# Sheet1.net
KiCad netlist of a schematic drawn in Altium Designer
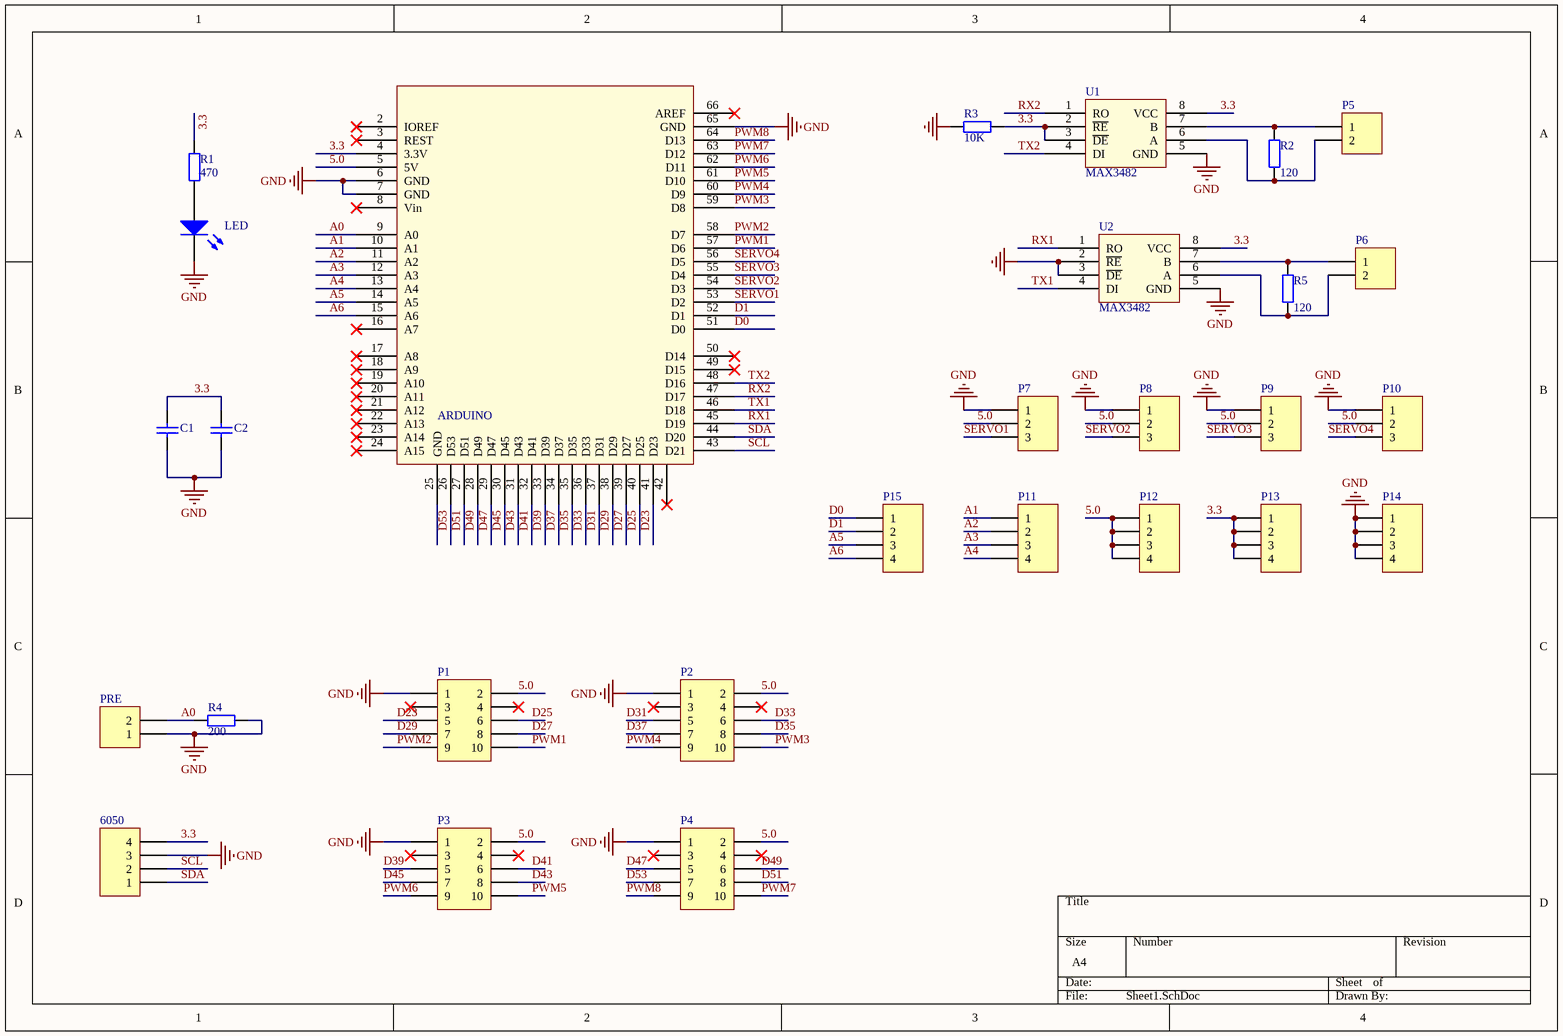
[diagram p0: Sheet1.SchDoc]

(export (version "E")
  (design (tool "Eeschema 10.0.6"))
  (components
    (comp (ref "6050")
      (value "Header 4")
      (footprint "HDR1X4")
      (description "Header, 4-Pin")
      (fields (field (name "PUBLISHER") "Altium Limited"))
      (libsource (lib "") (part "Header 4_1"))
    )
    (comp (ref "ARDUINO")
      (value "2560")
      (footprint "ARDUINO")
      (libsource (lib "Schlib1") (part "Component_1"))
    )
    (comp (ref "C1")
      (value "Cap")
      (footprint "0805")
      (description "Capacitor")
      (fields (field (name "PUBLISHER") "Altium Limited"))
      (libsource (lib "Miscellaneous Devices") (part "Cap"))
    )
    (comp (ref "C2")
      (value "Cap")
      (footprint "0805")
      (description "Capacitor")
      (fields (field (name "PUBLISHER") "Altium Limited"))
      (libsource (lib "Miscellaneous Devices") (part "Cap"))
    )
    (comp (ref "LED")
      (value "LED0")
      (footprint "0805")
      (description "Typical INFRARED GaAs LED")
      (fields (field (name "PUBLISHER") "Altium Limited"))
      (libsource (lib "Miscellaneous Devices") (part "LED0"))
    )
    (comp (ref "P1")
      (value "Header 5X2")
      (footprint "HDR2X5")
      (description "Header, 5-Pin, Dual row")
      (fields (field (name "PUBLISHER") "Altium Limited"))
      (libsource (lib "Miscellaneous Connectors") (part "Header 5X2"))
    )
    (comp (ref "P2")
      (value "Header 5X2")
      (footprint "HDR2X5")
      (description "Header, 5-Pin, Dual row")
      (fields (field (name "PUBLISHER") "Altium Limited"))
      (libsource (lib "Miscellaneous Connectors") (part "Header 5X2"))
    )
    (comp (ref "P3")
      (value "Header 5X2")
      (footprint "HDR2X5")
      (description "Header, 5-Pin, Dual row")
      (fields (field (name "PUBLISHER") "Altium Limited"))
      (libsource (lib "Miscellaneous Connectors") (part "Header 5X2"))
    )
    (comp (ref "P4")
      (value "Header 5X2")
      (footprint "HDR2X5")
      (description "Header, 5-Pin, Dual row")
      (fields (field (name "PUBLISHER") "Altium Limited"))
      (libsource (lib "Miscellaneous Connectors") (part "Header 5X2"))
    )
    (comp (ref "P5")
      (value "Header 2")
      (footprint "蓝色电源插座")
      (description "Header, 2-Pin")
      (fields (field (name "PUBLISHER") "Altium Limited"))
      (libsource (lib "Miscellaneous Connectors") (part "Header 2"))
    )
    (comp (ref "P6")
      (value "Header 2")
      (footprint "蓝色电源插座")
      (description "Header, 2-Pin")
      (fields (field (name "PUBLISHER") "Altium Limited"))
      (libsource (lib "Miscellaneous Connectors") (part "Header 2"))
    )
    (comp (ref "P7")
      (value "Header 3")
      (footprint "HDR1X3")
      (description "Header, 3-Pin")
      (fields (field (name "PUBLISHER") "Altium Limited"))
      (libsource (lib "Miscellaneous Connectors") (part "Header 3"))
    )
    (comp (ref "P8")
      (value "Header 3")
      (footprint "HDR1X3")
      (description "Header, 3-Pin")
      (fields (field (name "PUBLISHER") "Altium Limited"))
      (libsource (lib "Miscellaneous Connectors") (part "Header 3"))
    )
    (comp (ref "P9")
      (value "Header 3")
      (footprint "HDR1X3")
      (description "Header, 3-Pin")
      (fields (field (name "PUBLISHER") "Altium Limited"))
      (libsource (lib "Miscellaneous Connectors") (part "Header 3"))
    )
    (comp (ref "P10")
      (value "Header 3")
      (footprint "HDR1X3")
      (description "Header, 3-Pin")
      (fields (field (name "PUBLISHER") "Altium Limited"))
      (libsource (lib "Miscellaneous Connectors") (part "Header 3"))
    )
    (comp (ref "P11")
      (value "Header 4")
      (footprint "HDR1X4")
      (description "Header, 4-Pin")
      (fields (field (name "PUBLISHER") "Altium Limited"))
      (libsource (lib "Miscellaneous Connectors") (part "Header 4"))
    )
    (comp (ref "P12")
      (value "Header 4")
      (footprint "HDR1X4")
      (description "Header, 4-Pin")
      (fields (field (name "PUBLISHER") "Altium Limited"))
      (libsource (lib "Miscellaneous Connectors") (part "Header 4"))
    )
    (comp (ref "P13")
      (value "Header 4")
      (footprint "HDR1X4")
      (description "Header, 4-Pin")
      (fields (field (name "PUBLISHER") "Altium Limited"))
      (libsource (lib "Miscellaneous Connectors") (part "Header 4"))
    )
    (comp (ref "P14")
      (value "Header 4")
      (footprint "HDR1X4")
      (description "Header, 4-Pin")
      (fields (field (name "PUBLISHER") "Altium Limited"))
      (libsource (lib "Miscellaneous Connectors") (part "Header 4"))
    )
    (comp (ref "P15")
      (value "Header 4")
      (footprint "HDR1X4")
      (description "Header, 4-Pin")
      (fields (field (name "PUBLISHER") "Altium Limited"))
      (libsource (lib "Miscellaneous Connectors") (part "Header 4"))
    )
    (comp (ref "PRE")
      (value "Header 2")
      (footprint "HDR1X2")
      (description "Header, 2-Pin")
      (fields (field (name "PUBLISHER") "Altium Limited"))
      (libsource (lib "") (part "Header 2_1"))
    )
    (comp (ref "R1")
      (value "470")
      (footprint "0805")
      (description "Resistor")
      (fields (field (name "Comment") "Res2") (field (name "PUBLISHER") "Altium Limited"))
      (libsource (lib "") (part "Res2_3"))
    )
    (comp (ref "R2")
      (value "120")
      (footprint "0805")
      (description "Resistor")
      (fields (field (name "Comment") "Res2") (field (name "PUBLISHER") "Altium Limited"))
      (libsource (lib "") (part "Res2_1"))
    )
    (comp (ref "R3")
      (value "10K")
      (footprint "0805")
      (description "Resistor")
      (fields (field (name "Comment") "Res2") (field (name "PUBLISHER") "Altium Limited"))
      (libsource (lib "") (part "Res2_2"))
    )
    (comp (ref "R4")
      (value "200")
      (footprint "0805")
      (description "Resistor")
      (fields (field (name "Comment") "Res2") (field (name "PUBLISHER") "Altium Limited"))
      (libsource (lib "Miscellaneous Devices") (part "Res2"))
    )
    (comp (ref "R5")
      (value "120")
      (footprint "0805")
      (description "Resistor")
      (fields (field (name "Comment") "Res2") (field (name "PUBLISHER") "Altium Limited"))
      (libsource (lib "") (part "Res2_1"))
    )
    (comp (ref "U1") (value "MAX3482") (footprint "3485") (libsource (lib "Schlib1") (part "MAX3482")))
    (comp (ref "U2") (value "MAX3482") (footprint "3485") (libsource (lib "Schlib1") (part "MAX3482")))
  )
  (nets
    (net (code "1") (name "/3.3") (class "Default")
      (node (ref "6050") (pin "4") (pinfunction "4_4") (pintype "passive"))
      (node (ref "ARDUINO") (pin "4") (pinfunction "3.3V_4") (pintype "passive"))
      (node (ref "C1") (pin "2") (pinfunction "2_2") (pintype "passive"))
      (node (ref "C2") (pin "2") (pinfunction "2_2") (pintype "passive"))
      (node (ref "P13") (pin "1") (pinfunction "1_1") (pintype "passive"))
      (node (ref "P13") (pin "2") (pinfunction "2_2") (pintype "passive"))
      (node (ref "P13") (pin "3") (pinfunction "3_3") (pintype "passive"))
      (node (ref "P13") (pin "4") (pinfunction "4_4") (pintype "passive"))
      (node (ref "R1") (pin "1") (pinfunction "1_1") (pintype "passive"))
      (node (ref "R3") (pin "1") (pinfunction "1_1") (pintype "passive"))
      (node (ref "U1") (pin "2") (pinfunction "~{RE}_2") (pintype "passive"))
      (node (ref "U1") (pin "3") (pinfunction "~{DE}_3") (pintype "passive"))
      (node (ref "U1") (pin "8") (pinfunction "VCC_8") (pintype "passive"))
      (node (ref "U2") (pin "8") (pinfunction "VCC_8") (pintype "passive"))
    )
    (net (code "2") (name "/5.0") (class "Default")
      (node (ref "ARDUINO") (pin "5") (pinfunction "5V_5") (pintype "passive"))
      (node (ref "P1") (pin "2") (pinfunction "2_2") (pintype "passive"))
      (node (ref "P10") (pin "2") (pinfunction "2_2") (pintype "passive"))
      (node (ref "P12") (pin "1") (pinfunction "1_1") (pintype "passive"))
      (node (ref "P12") (pin "2") (pinfunction "2_2") (pintype "passive"))
      (node (ref "P12") (pin "3") (pinfunction "3_3") (pintype "passive"))
      (node (ref "P12") (pin "4") (pinfunction "4_4") (pintype "passive"))
      (node (ref "P2") (pin "2") (pinfunction "2_2") (pintype "passive"))
      (node (ref "P3") (pin "2") (pinfunction "2_2") (pintype "passive"))
      (node (ref "P4") (pin "2") (pinfunction "2_2") (pintype "passive"))
      (node (ref "P7") (pin "2") (pinfunction "2_2") (pintype "passive"))
      (node (ref "P8") (pin "2") (pinfunction "2_2") (pintype "passive"))
      (node (ref "P9") (pin "2") (pinfunction "2_2") (pintype "passive"))
    )
    (net (code "3") (name "/A0") (class "Default")
      (node (ref "ARDUINO") (pin "9") (pinfunction "A0_9") (pintype "passive"))
      (node (ref "PRE") (pin "2") (pinfunction "2_2") (pintype "passive"))
      (node (ref "R4") (pin "1") (pinfunction "1_1") (pintype "passive"))
    )
    (net (code "4") (name "/A1") (class "Default")
      (node (ref "ARDUINO") (pin "10") (pinfunction "A1_10") (pintype "passive"))
      (node (ref "P11") (pin "1") (pinfunction "1_1") (pintype "passive"))
    )
    (net (code "5") (name "/A2") (class "Default")
      (node (ref "ARDUINO") (pin "11") (pinfunction "A2_11") (pintype "passive"))
      (node (ref "P11") (pin "2") (pinfunction "2_2") (pintype "passive"))
    )
    (net (code "6") (name "/A3") (class "Default")
      (node (ref "ARDUINO") (pin "12") (pinfunction "A3_12") (pintype "passive"))
      (node (ref "P11") (pin "3") (pinfunction "3_3") (pintype "passive"))
    )
    (net (code "7") (name "/A4") (class "Default")
      (node (ref "ARDUINO") (pin "13") (pinfunction "A4_13") (pintype "passive"))
      (node (ref "P11") (pin "4") (pinfunction "4_4") (pintype "passive"))
    )
    (net (code "8") (name "/A5") (class "Default")
      (node (ref "ARDUINO") (pin "14") (pinfunction "A5_14") (pintype "passive"))
      (node (ref "P15") (pin "3") (pinfunction "3_3") (pintype "passive"))
    )
    (net (code "9") (name "/A6") (class "Default")
      (node (ref "ARDUINO") (pin "15") (pinfunction "A6_15") (pintype "passive"))
      (node (ref "P15") (pin "4") (pinfunction "4_4") (pintype "passive"))
    )
    (net (code "10") (name "/D0") (class "Default")
      (node (ref "ARDUINO") (pin "51") (pinfunction "D0_51") (pintype "passive"))
      (node (ref "P15") (pin "1") (pinfunction "1_1") (pintype "passive"))
    )
    (net (code "11") (name "/D1") (class "Default")
      (node (ref "ARDUINO") (pin "52") (pinfunction "D1_52") (pintype "passive"))
      (node (ref "P15") (pin "2") (pinfunction "2_2") (pintype "passive"))
    )
    (net (code "12") (name "/D23") (class "Default")
      (node (ref "ARDUINO") (pin "41") (pinfunction "D23_41") (pintype "passive"))
      (node (ref "P1") (pin "5") (pinfunction "5_5") (pintype "passive"))
    )
    (net (code "13") (name "/D25") (class "Default")
      (node (ref "ARDUINO") (pin "40") (pinfunction "D25_40") (pintype "passive"))
      (node (ref "P1") (pin "6") (pinfunction "6_6") (pintype "passive"))
    )
    (net (code "14") (name "/D27") (class "Default")
      (node (ref "ARDUINO") (pin "39") (pinfunction "D27_39") (pintype "passive"))
      (node (ref "P1") (pin "8") (pinfunction "8_8") (pintype "passive"))
    )
    (net (code "15") (name "/D29") (class "Default")
      (node (ref "ARDUINO") (pin "38") (pinfunction "D29_38") (pintype "passive"))
      (node (ref "P1") (pin "7") (pinfunction "7_7") (pintype "passive"))
    )
    (net (code "16") (name "/D31") (class "Default")
      (node (ref "ARDUINO") (pin "37") (pinfunction "D31_37") (pintype "passive"))
      (node (ref "P2") (pin "5") (pinfunction "5_5") (pintype "passive"))
    )
    (net (code "17") (name "/D33") (class "Default")
      (node (ref "ARDUINO") (pin "36") (pinfunction "D33_36") (pintype "passive"))
      (node (ref "P2") (pin "6") (pinfunction "6_6") (pintype "passive"))
    )
    (net (code "18") (name "/D35") (class "Default")
      (node (ref "ARDUINO") (pin "35") (pinfunction "D35_35") (pintype "passive"))
      (node (ref "P2") (pin "8") (pinfunction "8_8") (pintype "passive"))
    )
    (net (code "19") (name "/D37") (class "Default")
      (node (ref "ARDUINO") (pin "34") (pinfunction "D37_34") (pintype "passive"))
      (node (ref "P2") (pin "7") (pinfunction "7_7") (pintype "passive"))
    )
    (net (code "20") (name "/D39") (class "Default")
      (node (ref "ARDUINO") (pin "33") (pinfunction "D39_33") (pintype "passive"))
      (node (ref "P3") (pin "5") (pinfunction "5_5") (pintype "passive"))
    )
    (net (code "21") (name "/D41") (class "Default")
      (node (ref "ARDUINO") (pin "32") (pinfunction "D41_32") (pintype "passive"))
      (node (ref "P3") (pin "6") (pinfunction "6_6") (pintype "passive"))
    )
    (net (code "22") (name "/D43") (class "Default")
      (node (ref "ARDUINO") (pin "31") (pinfunction "D43_31") (pintype "passive"))
      (node (ref "P3") (pin "8") (pinfunction "8_8") (pintype "passive"))
    )
    (net (code "23") (name "/D45") (class "Default")
      (node (ref "ARDUINO") (pin "30") (pinfunction "D45_30") (pintype "passive"))
      (node (ref "P3") (pin "7") (pinfunction "7_7") (pintype "passive"))
    )
    (net (code "24") (name "/D47") (class "Default")
      (node (ref "ARDUINO") (pin "29") (pinfunction "D47_29") (pintype "passive"))
      (node (ref "P4") (pin "5") (pinfunction "5_5") (pintype "passive"))
    )
    (net (code "25") (name "/D49") (class "Default")
      (node (ref "ARDUINO") (pin "28") (pinfunction "D49_28") (pintype "passive"))
      (node (ref "P4") (pin "6") (pinfunction "6_6") (pintype "passive"))
    )
    (net (code "26") (name "/D51") (class "Default")
      (node (ref "ARDUINO") (pin "27") (pinfunction "D51_27") (pintype "passive"))
      (node (ref "P4") (pin "8") (pinfunction "8_8") (pintype "passive"))
    )
    (net (code "27") (name "/D53") (class "Default")
      (node (ref "ARDUINO") (pin "26") (pinfunction "D53_26") (pintype "passive"))
      (node (ref "P4") (pin "7") (pinfunction "7_7") (pintype "passive"))
    )
    (net (code "28") (name "/PWM1") (class "Default")
      (node (ref "ARDUINO") (pin "57") (pinfunction "D6_57") (pintype "passive"))
      (node (ref "P1") (pin "10") (pinfunction "10_10") (pintype "passive"))
    )
    (net (code "29") (name "/PWM2") (class "Default")
      (node (ref "ARDUINO") (pin "58") (pinfunction "D7_58") (pintype "passive"))
      (node (ref "P1") (pin "9") (pinfunction "9_9") (pintype "passive"))
    )
    (net (code "30") (name "/PWM3") (class "Default")
      (node (ref "ARDUINO") (pin "59") (pinfunction "D8_59") (pintype "passive"))
      (node (ref "P2") (pin "10") (pinfunction "10_10") (pintype "passive"))
    )
    (net (code "31") (name "/PWM4") (class "Default")
      (node (ref "ARDUINO") (pin "60") (pinfunction "D9_60") (pintype "passive"))
      (node (ref "P2") (pin "9") (pinfunction "9_9") (pintype "passive"))
    )
    (net (code "32") (name "/PWM5") (class "Default")
      (node (ref "ARDUINO") (pin "61") (pinfunction "D10_61") (pintype "passive"))
      (node (ref "P3") (pin "10") (pinfunction "10_10") (pintype "passive"))
    )
    (net (code "33") (name "/PWM6") (class "Default")
      (node (ref "ARDUINO") (pin "62") (pinfunction "D11_62") (pintype "passive"))
      (node (ref "P3") (pin "9") (pinfunction "9_9") (pintype "passive"))
    )
    (net (code "34") (name "/PWM7") (class "Default")
      (node (ref "ARDUINO") (pin "63") (pinfunction "D12_63") (pintype "passive"))
      (node (ref "P4") (pin "10") (pinfunction "10_10") (pintype "passive"))
    )
    (net (code "35") (name "/PWM8") (class "Default")
      (node (ref "ARDUINO") (pin "64") (pinfunction "D13_64") (pintype "passive"))
      (node (ref "P4") (pin "9") (pinfunction "9_9") (pintype "passive"))
    )
    (net (code "36") (name "/RX1") (class "Default")
      (node (ref "ARDUINO") (pin "45") (pinfunction "D19_45") (pintype "passive"))
      (node (ref "U2") (pin "1") (pinfunction "RO_1") (pintype "passive"))
    )
    (net (code "37") (name "/RX2") (class "Default")
      (node (ref "ARDUINO") (pin "47") (pinfunction "D17_47") (pintype "passive"))
      (node (ref "U1") (pin "1") (pinfunction "RO_1") (pintype "passive"))
    )
    (net (code "38") (name "/SCL") (class "Default")
      (node (ref "6050") (pin "2") (pinfunction "2_2") (pintype "passive"))
      (node (ref "ARDUINO") (pin "43") (pinfunction "D21_43") (pintype "passive"))
    )
    (net (code "39") (name "/SDA") (class "Default")
      (node (ref "6050") (pin "1") (pinfunction "1_1") (pintype "passive"))
      (node (ref "ARDUINO") (pin "44") (pinfunction "D20_44") (pintype "passive"))
    )
    (net (code "40") (name "/SERVO1") (class "Default")
      (node (ref "ARDUINO") (pin "53") (pinfunction "D2_53") (pintype "passive"))
      (node (ref "P7") (pin "3") (pinfunction "3_3") (pintype "passive"))
    )
    (net (code "41") (name "/SERVO2") (class "Default")
      (node (ref "ARDUINO") (pin "54") (pinfunction "D3_54") (pintype "passive"))
      (node (ref "P8") (pin "3") (pinfunction "3_3") (pintype "passive"))
    )
    (net (code "42") (name "/SERVO3") (class "Default")
      (node (ref "ARDUINO") (pin "55") (pinfunction "D4_55") (pintype "passive"))
      (node (ref "P9") (pin "3") (pinfunction "3_3") (pintype "passive"))
    )
    (net (code "43") (name "/SERVO4") (class "Default")
      (node (ref "ARDUINO") (pin "56") (pinfunction "D5_56") (pintype "passive"))
      (node (ref "P10") (pin "3") (pinfunction "3_3") (pintype "passive"))
    )
    (net (code "44") (name "/TX1") (class "Default")
      (node (ref "ARDUINO") (pin "46") (pinfunction "D18_46") (pintype "passive"))
      (node (ref "U2") (pin "4") (pinfunction "DI_4") (pintype "passive"))
    )
    (net (code "45") (name "/TX2") (class "Default")
      (node (ref "ARDUINO") (pin "48") (pinfunction "D16_48") (pintype "passive"))
      (node (ref "U1") (pin "4") (pinfunction "DI_4") (pintype "passive"))
    )
    (net (code "46") (name "GND") (class "Default")
      (node (ref "6050") (pin "3") (pinfunction "3_3") (pintype "passive"))
      (node (ref "ARDUINO") (pin "6") (pinfunction "GND_6") (pintype "passive"))
      (node (ref "ARDUINO") (pin "65") (pinfunction "GND_65") (pintype "passive"))
      (node (ref "ARDUINO") (pin "7") (pinfunction "GND_7") (pintype "passive"))
      (node (ref "C1") (pin "1") (pinfunction "1_1") (pintype "passive"))
      (node (ref "C2") (pin "1") (pinfunction "1_1") (pintype "passive"))
      (node (ref "LED") (pin "2") (pinfunction "K_2") (pintype "passive"))
      (node (ref "P1") (pin "1") (pinfunction "1_1") (pintype "passive"))
      (node (ref "P10") (pin "1") (pinfunction "1_1") (pintype "passive"))
      (node (ref "P14") (pin "1") (pinfunction "1_1") (pintype "passive"))
      (node (ref "P14") (pin "2") (pinfunction "2_2") (pintype "passive"))
      (node (ref "P14") (pin "3") (pinfunction "3_3") (pintype "passive"))
      (node (ref "P14") (pin "4") (pinfunction "4_4") (pintype "passive"))
      (node (ref "P2") (pin "1") (pinfunction "1_1") (pintype "passive"))
      (node (ref "P3") (pin "1") (pinfunction "1_1") (pintype "passive"))
      (node (ref "P4") (pin "1") (pinfunction "1_1") (pintype "passive"))
      (node (ref "P7") (pin "1") (pinfunction "1_1") (pintype "passive"))
      (node (ref "P8") (pin "1") (pinfunction "1_1") (pintype "passive"))
      (node (ref "P9") (pin "1") (pinfunction "1_1") (pintype "passive"))
      (node (ref "PRE") (pin "1") (pinfunction "1_1") (pintype "passive"))
      (node (ref "R3") (pin "2") (pinfunction "2_2") (pintype "passive"))
      (node (ref "R4") (pin "2") (pinfunction "2_2") (pintype "passive"))
      (node (ref "U1") (pin "5") (pinfunction "GND_5") (pintype "passive"))
      (node (ref "U2") (pin "2") (pinfunction "~{RE}_2") (pintype "passive"))
      (node (ref "U2") (pin "3") (pinfunction "~{DE}_3") (pintype "passive"))
      (node (ref "U2") (pin "5") (pinfunction "GND_5") (pintype "passive"))
    )
    (net (code "47") (name "Net-(LED-A)") (class "Default")
      (node (ref "LED") (pin "1") (pinfunction "A_1") (pintype "passive"))
      (node (ref "R1") (pin "2") (pinfunction "2_2") (pintype "passive"))
    )
    (net (code "48") (name "Net-(P5-1)") (class "Default")
      (node (ref "P5") (pin "2") (pinfunction "1_2") (pintype "passive"))
      (node (ref "R2") (pin "2") (pinfunction "2_2") (pintype "passive"))
      (node (ref "U1") (pin "7") (pinfunction "B_7") (pintype "passive"))
    )
    (net (code "49") (name "Net-(P5-2)") (class "Default")
      (node (ref "P5") (pin "1") (pinfunction "2_1") (pintype "passive"))
      (node (ref "R2") (pin "1") (pinfunction "1_1") (pintype "passive"))
      (node (ref "U1") (pin "6") (pinfunction "A_6") (pintype "passive"))
    )
    (net (code "50") (name "Net-(P6-1)") (class "Default")
      (node (ref "P6") (pin "2") (pinfunction "1_2") (pintype "passive"))
      (node (ref "R5") (pin "2") (pinfunction "2_2") (pintype "passive"))
      (node (ref "U2") (pin "7") (pinfunction "B_7") (pintype "passive"))
    )
    (net (code "51") (name "Net-(P6-2)") (class "Default")
      (node (ref "P6") (pin "1") (pinfunction "2_1") (pintype "passive"))
      (node (ref "R5") (pin "1") (pinfunction "1_1") (pintype "passive"))
      (node (ref "U2") (pin "6") (pinfunction "A_6") (pintype "passive"))
    )
    (net (code "52") (name "unconnected-(ARDUINO-A7-Pad16)") (class "Default")
      (node (ref "ARDUINO") (pin "16") (pinfunction "A7_16") (pintype "passive+no_connect"))
    )
    (net (code "53") (name "unconnected-(ARDUINO-A8-Pad17)") (class "Default")
      (node (ref "ARDUINO") (pin "17") (pinfunction "A8_17") (pintype "passive+no_connect"))
    )
    (net (code "54") (name "unconnected-(ARDUINO-A9-Pad18)") (class "Default")
      (node (ref "ARDUINO") (pin "18") (pinfunction "A9_18") (pintype "passive+no_connect"))
    )
    (net (code "55") (name "unconnected-(ARDUINO-A10-Pad19)") (class "Default")
      (node (ref "ARDUINO") (pin "19") (pinfunction "A10_19") (pintype "passive+no_connect"))
    )
    (net (code "56") (name "unconnected-(ARDUINO-A11-Pad20)") (class "Default")
      (node (ref "ARDUINO") (pin "20") (pinfunction "A11_20") (pintype "passive+no_connect"))
    )
    (net (code "57") (name "unconnected-(ARDUINO-A12-Pad21)") (class "Default")
      (node (ref "ARDUINO") (pin "21") (pinfunction "A12_21") (pintype "passive+no_connect"))
    )
    (net (code "58") (name "unconnected-(ARDUINO-A13-Pad22)") (class "Default")
      (node (ref "ARDUINO") (pin "22") (pinfunction "A13_22") (pintype "passive+no_connect"))
    )
    (net (code "59") (name "unconnected-(ARDUINO-A14-Pad23)") (class "Default")
      (node (ref "ARDUINO") (pin "23") (pinfunction "A14_23") (pintype "passive+no_connect"))
    )
    (net (code "60") (name "unconnected-(ARDUINO-A15-Pad24)") (class "Default")
      (node (ref "ARDUINO") (pin "24") (pinfunction "A15_24") (pintype "passive+no_connect"))
    )
    (net (code "61") (name "unconnected-(ARDUINO-AREF-Pad66)") (class "Default")
      (node (ref "ARDUINO") (pin "66") (pinfunction "AREF_66") (pintype "passive+no_connect"))
    )
    (net (code "62") (name "unconnected-(ARDUINO-D14-Pad50)") (class "Default")
      (node (ref "ARDUINO") (pin "50") (pinfunction "D14_50") (pintype "passive+no_connect"))
    )
    (net (code "63") (name "unconnected-(ARDUINO-D15-Pad49)") (class "Default")
      (node (ref "ARDUINO") (pin "49") (pinfunction "D15_49") (pintype "passive+no_connect"))
    )
    (net (code "64") (name "unconnected-(ARDUINO-GND-Pad25)") (class "Default")
      (node (ref "ARDUINO") (pin "25") (pinfunction "GND_25") (pintype "passive"))
    )
    (net (code "65") (name "unconnected-(ARDUINO-IOREF-Pad2)") (class "Default")
      (node (ref "ARDUINO") (pin "2") (pinfunction "IOREF_2") (pintype "passive+no_connect"))
    )
    (net (code "66") (name "unconnected-(ARDUINO-Pad42)") (class "Default")
      (node (ref "ARDUINO") (pin "42") (pintype "passive+no_connect"))
    )
    (net (code "67") (name "unconnected-(ARDUINO-REST-Pad3)") (class "Default")
      (node (ref "ARDUINO") (pin "3") (pinfunction "REST_3") (pintype "passive+no_connect"))
    )
    (net (code "68") (name "unconnected-(ARDUINO-Vin-Pad8)") (class "Default")
      (node (ref "ARDUINO") (pin "8") (pinfunction "Vin_8") (pintype "passive+no_connect"))
    )
    (net (code "69") (name "unconnected-(P1-Pad3)") (class "Default")
      (node (ref "P1") (pin "3") (pinfunction "3_3") (pintype "passive+no_connect"))
    )
    (net (code "70") (name "unconnected-(P1-Pad4)") (class "Default")
      (node (ref "P1") (pin "4") (pinfunction "4_4") (pintype "passive+no_connect"))
    )
    (net (code "71") (name "unconnected-(P2-Pad3)") (class "Default")
      (node (ref "P2") (pin "3") (pinfunction "3_3") (pintype "passive+no_connect"))
    )
    (net (code "72") (name "unconnected-(P2-Pad4)") (class "Default")
      (node (ref "P2") (pin "4") (pinfunction "4_4") (pintype "passive+no_connect"))
    )
    (net (code "73") (name "unconnected-(P3-Pad3)") (class "Default")
      (node (ref "P3") (pin "3") (pinfunction "3_3") (pintype "passive+no_connect"))
    )
    (net (code "74") (name "unconnected-(P3-Pad4)") (class "Default")
      (node (ref "P3") (pin "4") (pinfunction "4_4") (pintype "passive+no_connect"))
    )
    (net (code "75") (name "unconnected-(P4-Pad3)") (class "Default")
      (node (ref "P4") (pin "3") (pinfunction "3_3") (pintype "passive+no_connect"))
    )
    (net (code "76") (name "unconnected-(P4-Pad4)") (class "Default")
      (node (ref "P4") (pin "4") (pinfunction "4_4") (pintype "passive+no_connect"))
    )
  )
)
